# 3_3V_Regulator.net
KiCad netlist of a schematic drawn in Altium Designer
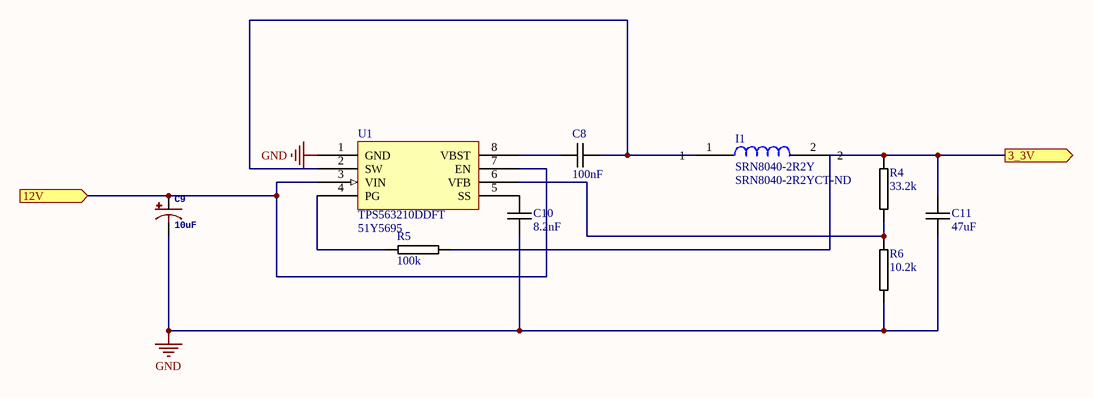
[diagram p0: 3_3V Regulator.SchDoc]

(export (version "E")
  (design (tool "Eeschema 10.0.6"))
  (components
    (comp (ref "C8")
      (value "100nF")
      (footprint "0805C-TBD")
      (description "CAPACITOR 0805 CERAMIC")
      (fields
        (field (name "MANUFACTURER PART NUMBER") "ECJ-1VB0J225K")
        (field (name "MANUFACTURER") "Panasonic - ECG")
      )
      (libsource (lib "vh_altium_library") (part "0603C-2U2-6V3-X5R-PAN"))
    )
    (comp (ref "C9")
      (value "10uF")
      (footprint "EIA3216")
      (libsource (lib "SparkFun-Retired") (part "10UF-TANT"))
    )
    (comp (ref "C10")
      (value "8.2nF")
      (footprint "0603C-GENERIC")
      (description "CAPACITOR 0603 CERAMIC")
      (libsource (lib "vh_altium_library") (part "0603C-000"))
    )
    (comp (ref "C11")
      (value "47uF")
      (footprint "0805C-TBD")
      (description "CAPACITOR 0805 CERAMIC")
      (fields
        (field (name "MANUFACTURER PART NUMBER") "ECJ-1VB0J225K")
        (field (name "MANUFACTURER") "Panasonic - ECG")
      )
      (libsource (lib "vh_altium_library") (part "0603C-2U2-6V3-X5R-PAN"))
    )
    (comp (ref "I1")
      (value "SRN8040-2R2Y")
      (footprint "SRN8040")
      (description "FIXED IND 2.2UH 6.3A 13 MOHM SMD")
      (fields
        (field (name "MANUFACTURER") "Bourns Inc.")
        (field (name "TOLERANCE") "±30%")
        (field (name "SUPPLIER PART NUMBER 1") "SRN8040-2R2YCT-ND")
      )
      (libsource (lib "Digi_Key") (part "SRN8040-2R2Y"))
    )
    (comp (ref "R4")
      (value "33.2k")
      (footprint "0402R-TBD")
      (description "RESISTOR 0402 VALUE TO BE DETERMINED")
      (libsource (lib "vh_altium_library") (part "0402R-TBD"))
    )
    (comp (ref "R5")
      (value "100k")
      (footprint "0402R-TBD")
      (description "RESISTOR 0402 VALUE TO BE DETERMINED")
      (libsource (lib "vh_altium_library") (part "0402R-TBD"))
    )
    (comp (ref "R6")
      (value "10.2k")
      (footprint "0402R-TBD")
      (description "RESISTOR 0402 VALUE TO BE DETERMINED")
      (libsource (lib "vh_altium_library") (part "0402R-TBD"))
    )
    (comp (ref "U1")
      (value "TPS563210DDFT")
      (footprint "SOT23-8")
      (description "TEXAS INSTRUMENTS - TPS563210DDFT - DC/DC CONV, SYNC BUCK, 650KHZ, SOT-23-8")
      (fields
        (field (name "MANUFACTURER") "TEXAS INSTRUMENTS")
        (field (name "SUPPLIER PART NUMBER 1") "51Y5695")
      )
      (libsource (lib "Digi_Key") (part "TPS563210DDFT"))
    )
  )
  (nets
    (net (code "1") (name "/3_3V") (class "Default")
      (node (ref "C11") (pin "2") (pintype "passive"))
      (node (ref "R4") (pin "1") (pintype "passive"))
      (node (ref "R5") (pin "2") (pintype "passive"))
    )
    (net (code "2") (name "/12V") (class "Default")
      (node (ref "C9") (pin "A") (pinfunction "+_A") (pintype "passive"))
      (node (ref "U1") (pin "3") (pinfunction "VIN_3") (pintype "input"))
      (node (ref "U1") (pin "7") (pinfunction "EN_7") (pintype "passive"))
    )
    (net (code "3") (name "GND") (class "Default")
      (node (ref "C10") (pin "2") (pintype "passive"))
      (node (ref "C11") (pin "1") (pintype "passive"))
      (node (ref "C9") (pin "C") (pinfunction "-_C") (pintype "passive"))
      (node (ref "R6") (pin "2") (pintype "passive"))
      (node (ref "U1") (pin "1") (pinfunction "GND_1") (pintype "passive"))
    )
    (net (code "4") (name "Net-(U1-PG)") (class "Default")
      (node (ref "R5") (pin "1") (pintype "passive"))
      (node (ref "U1") (pin "4") (pinfunction "PG_4") (pintype "passive"))
    )
    (net (code "5") (name "Net-(U1-SS)") (class "Default")
      (node (ref "C10") (pin "1") (pintype "passive"))
      (node (ref "U1") (pin "5") (pinfunction "SS_5") (pintype "passive"))
    )
    (net (code "6") (name "Net-(U1-SW)") (class "Default")
      (node (ref "C8") (pin "2") (pintype "passive"))
      (node (ref "U1") (pin "2") (pinfunction "SW_2") (pintype "passive"))
    )
    (net (code "7") (name "Net-(U1-VBST)") (class "Default")
      (node (ref "C8") (pin "1") (pintype "passive"))
      (node (ref "U1") (pin "8") (pinfunction "VBST_8") (pintype "passive"))
    )
    (net (code "8") (name "Net-(U1-VFB)") (class "Default")
      (node (ref "R4") (pin "2") (pintype "passive"))
      (node (ref "R6") (pin "1") (pintype "passive"))
      (node (ref "U1") (pin "6") (pinfunction "VFB_6") (pintype "passive"))
    )
    (net (code "9") (name "unconnected-(I1-Pad1)") (class "Default")
      (node (ref "I1") (pin "1") (pinfunction "1_1") (pintype "passive"))
    )
    (net (code "10") (name "unconnected-(I1-Pad2)") (class "Default")
      (node (ref "I1") (pin "2") (pinfunction "2_2") (pintype "passive"))
    )
  )
)
